# CH1_CH2.net
KiCad netlist of a schematic drawn in Altium Designer
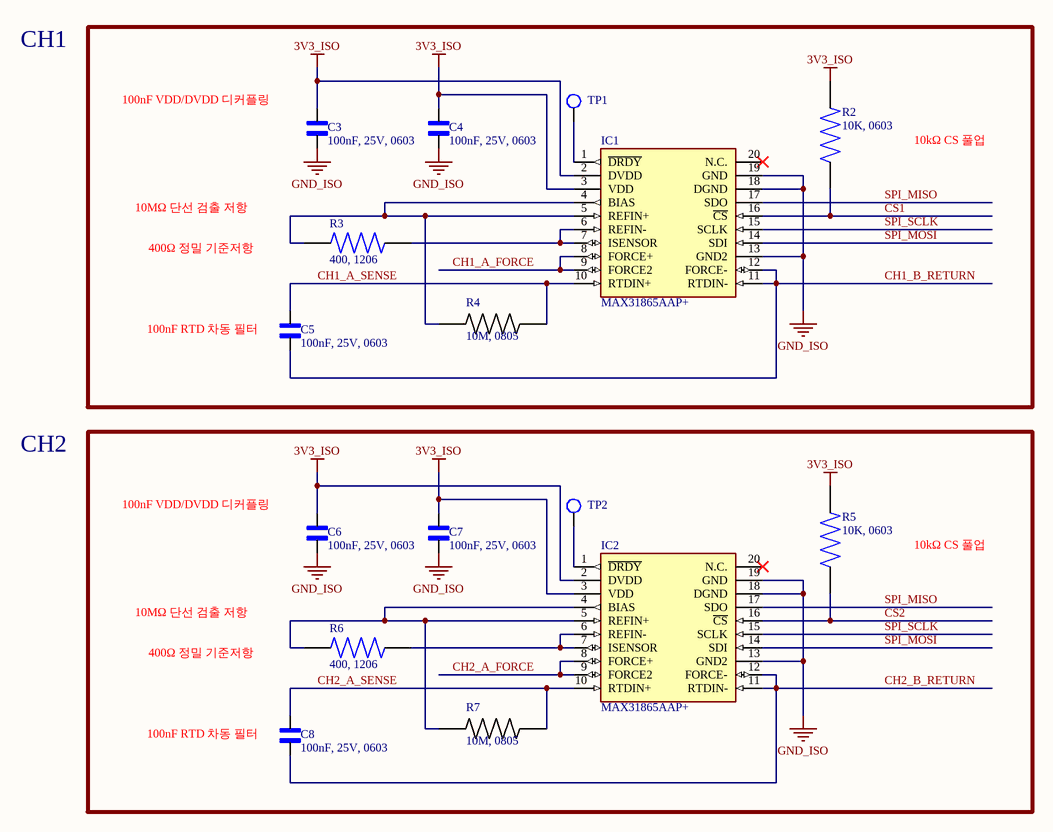
[diagram p0: CH1_CH2.SchDoc]

(export (version "E")
  (design (tool "Eeschema 10.0.6"))
  (components
    (comp (ref "C3")
      (value "100nF, 25V, 0603")
      (footprint "CAPC1608X90N")
      (description "Multilayer Ceramic Capacitors MLCC - SMD/SMT")
      (fields (field (name "MF") "Samsung Electro-Mechanics") (field (name "MP") "CL10B104KA8VPJC"))
      (libsource (lib "CL10B104KA8VPJC") (part "CL10B104KA8VPJC"))
    )
    (comp (ref "C4")
      (value "100nF, 25V, 0603")
      (footprint "CAPC1608X90N")
      (description "Multilayer Ceramic Capacitors MLCC - SMD/SMT")
      (fields (field (name "MF") "Samsung Electro-Mechanics") (field (name "MP") "CL10B104KA8VPJC"))
      (libsource (lib "CL10B104KA8VPJC") (part "CL10B104KA8VPJC"))
    )
    (comp (ref "C5")
      (value "100nF, 25V, 0603")
      (footprint "CAPC1608X90N")
      (description "Multilayer Ceramic Capacitors MLCC - SMD/SMT")
      (fields (field (name "MF") "Samsung Electro-Mechanics") (field (name "MP") "CL10B104KA8VPJC"))
      (libsource (lib "CL10B104KA8VPJC") (part "CL10B104KA8VPJC"))
    )
    (comp (ref "C6")
      (value "100nF, 25V, 0603")
      (footprint "CAPC1608X90N")
      (description "Multilayer Ceramic Capacitors MLCC - SMD/SMT")
      (fields (field (name "MF") "Samsung Electro-Mechanics") (field (name "MP") "CL10B104KA8VPJC"))
      (libsource (lib "CL10B104KA8VPJC") (part "CL10B104KA8VPJC"))
    )
    (comp (ref "C7")
      (value "100nF, 25V, 0603")
      (footprint "CAPC1608X90N")
      (description "Multilayer Ceramic Capacitors MLCC - SMD/SMT")
      (fields (field (name "MF") "Samsung Electro-Mechanics") (field (name "MP") "CL10B104KA8VPJC"))
      (libsource (lib "CL10B104KA8VPJC") (part "CL10B104KA8VPJC"))
    )
    (comp (ref "C8")
      (value "100nF, 25V, 0603")
      (footprint "CAPC1608X90N")
      (description "Multilayer Ceramic Capacitors MLCC - SMD/SMT")
      (fields (field (name "MF") "Samsung Electro-Mechanics") (field (name "MP") "CL10B104KA8VPJC"))
      (libsource (lib "CL10B104KA8VPJC") (part "CL10B104KA8VPJC"))
    )
    (comp (ref "IC1")
      (value "MAX31865AAP+")
      (footprint "SamacSys:SOP65P778X199-20N")
      (description "Integrated Circuit")
      (fields (field (name "MOUSER PART NUMBER") "700-MAX31865AAP+"))
      (libsource (lib "MAX31865AAP+") (part "MAX31865AAP+"))
    )
    (comp (ref "IC2")
      (value "MAX31865AAP+")
      (footprint "SamacSys:SOP65P778X199-20N")
      (description "Integrated Circuit")
      (fields (field (name "MOUSER PART NUMBER") "700-MAX31865AAP+"))
      (libsource (lib "MAX31865AAP+") (part "MAX31865AAP+"))
    )
    (comp (ref "R2")
      (value "10K, 0603")
      (footprint "RESC1607X60N")
      (description "10 kOhms ±1% 0.1W, 1/10W Chip Resistor 0603 (1608 Metric) Moisture Resistant Thick Film")
      (fields (field (name "MF") "Yageo Corporation") (field (name "MP") "RC0603FR0710KL"))
      (libsource (lib "RC0603FR-0710KL") (part "RC0603FR-0710KL"))
    )
    (comp (ref "R3")
      (value "400, 1206")
      (footprint "RESC3116X65N")
      (description "400 Ohms Â±0.1% 0.25W, 1/4W Chip Resistor 1206 (3216 Metric) - Thin Film")
      (fields (field (name "MF") "Yageo") (field (name "MP") "RT1206BRD07400RL"))
      (libsource (lib "RT1206BRD07400RL") (part "RT1206BRD07400RL"))
    )
    (comp (ref "R4")
      (value "10M, 0805")
      (footprint "*RESC2012X60N")
      (description "10MΩ, ±1%, 125mW, 0805, AEC-Q200")
      (libsource (lib "AC0805FR-1010ML") (part "AC0805FR-1010ML"))
    )
    (comp (ref "R5")
      (value "10K, 0603")
      (footprint "RESC1607X60N")
      (description "10 kOhms ±1% 0.1W, 1/10W Chip Resistor 0603 (1608 Metric) Moisture Resistant Thick Film")
      (fields (field (name "MF") "Yageo Corporation") (field (name "MP") "RC0603FR0710KL"))
      (libsource (lib "RC0603FR-0710KL") (part "RC0603FR-0710KL"))
    )
    (comp (ref "R6")
      (value "400, 1206")
      (footprint "RESC3116X65N")
      (description "400 Ohms Â±0.1% 0.25W, 1/4W Chip Resistor 1206 (3216 Metric) - Thin Film")
      (fields (field (name "MF") "Yageo") (field (name "MP") "RT1206BRD07400RL"))
      (libsource (lib "RT1206BRD07400RL") (part "RT1206BRD07400RL"))
    )
    (comp (ref "R7")
      (value "10M, 0805")
      (footprint "*RESC2012X60N")
      (description "10MΩ, ±1%, 125mW, 0805, AEC-Q200")
      (libsource (lib "AC0805FR-1010ML") (part "AC0805FR-1010ML"))
    )
    (comp (ref "TP1")
      (value "TEST POINT")
      (footprint "TESTPOINT")
      (libsource (lib "TP1.0-SMD") (part "TEST POINT"))
    )
    (comp (ref "TP2")
      (value "TEST POINT")
      (footprint "TESTPOINT")
      (libsource (lib "TP1.0-SMD") (part "TEST POINT"))
    )
  )
  (nets
    (net (code "1") (name "/CH1_A_FORCE") (class "Default")
      (node (ref "IC1") (pin "8") (pinfunction "FORCE+_8") (pintype "bidirectional"))
      (node (ref "IC1") (pin "9") (pinfunction "FORCE2_9") (pintype "bidirectional"))
    )
    (net (code "2") (name "/CH1_A_SENSE") (class "Default")
      (node (ref "C5") (pin "2") (pinfunction "2_2") (pintype "passive"))
      (node (ref "IC1") (pin "10") (pinfunction "RTDIN+_10") (pintype "input"))
      (node (ref "R4") (pin "2") (pinfunction "2_2") (pintype "passive"))
    )
    (net (code "3") (name "/CH1_B_RETURN") (class "Default")
      (node (ref "C5") (pin "1") (pinfunction "1_1") (pintype "passive"))
      (node (ref "IC1") (pin "11") (pinfunction "RTDIN-_11") (pintype "input"))
      (node (ref "IC1") (pin "12") (pinfunction "FORCE-_12") (pintype "bidirectional"))
    )
    (net (code "4") (name "/CH2_A_FORCE") (class "Default")
      (node (ref "IC2") (pin "8") (pinfunction "FORCE+_8") (pintype "bidirectional"))
      (node (ref "IC2") (pin "9") (pinfunction "FORCE2_9") (pintype "bidirectional"))
    )
    (net (code "5") (name "/CH2_A_SENSE") (class "Default")
      (node (ref "C8") (pin "2") (pinfunction "2_2") (pintype "passive"))
      (node (ref "IC2") (pin "10") (pinfunction "RTDIN+_10") (pintype "input"))
      (node (ref "R7") (pin "2") (pinfunction "2_2") (pintype "passive"))
    )
    (net (code "6") (name "/CH2_B_RETURN") (class "Default")
      (node (ref "C8") (pin "1") (pinfunction "1_1") (pintype "passive"))
      (node (ref "IC2") (pin "11") (pinfunction "RTDIN-_11") (pintype "input"))
      (node (ref "IC2") (pin "12") (pinfunction "FORCE-_12") (pintype "bidirectional"))
    )
    (net (code "7") (name "/CS1") (class "Default")
      (node (ref "IC1") (pin "16") (pinfunction "~{CS}_16") (pintype "input"))
      (node (ref "R2") (pin "1") (pinfunction "1_1") (pintype "passive"))
    )
    (net (code "8") (name "/CS2") (class "Default")
      (node (ref "IC2") (pin "16") (pinfunction "~{CS}_16") (pintype "input"))
      (node (ref "R5") (pin "1") (pinfunction "1_1") (pintype "passive"))
    )
    (net (code "9") (name "/SPI_MISO") (class "Default")
      (node (ref "IC1") (pin "17") (pinfunction "SDO_17") (pintype "tri_state"))
      (node (ref "IC2") (pin "17") (pinfunction "SDO_17") (pintype "tri_state"))
    )
    (net (code "10") (name "/SPI_MOSI") (class "Default")
      (node (ref "IC1") (pin "14") (pinfunction "SDI_14") (pintype "input"))
      (node (ref "IC2") (pin "14") (pinfunction "SDI_14") (pintype "input"))
    )
    (net (code "11") (name "/SPI_SCLK") (class "Default")
      (node (ref "IC1") (pin "15") (pinfunction "SCLK_15") (pintype "input"))
      (node (ref "IC2") (pin "15") (pinfunction "SCLK_15") (pintype "input"))
    )
    (net (code "12") (name "3V3_ISO") (class "Default")
      (node (ref "C3") (pin "2") (pinfunction "2_2") (pintype "passive"))
      (node (ref "C4") (pin "2") (pinfunction "2_2") (pintype "passive"))
      (node (ref "C6") (pin "2") (pinfunction "2_2") (pintype "passive"))
      (node (ref "C7") (pin "2") (pinfunction "2_2") (pintype "passive"))
      (node (ref "IC1") (pin "2") (pinfunction "DVDD_2") (pintype "power_in"))
      (node (ref "IC1") (pin "3") (pinfunction "VDD_3") (pintype "power_in"))
      (node (ref "IC2") (pin "2") (pinfunction "DVDD_2") (pintype "power_in"))
      (node (ref "IC2") (pin "3") (pinfunction "VDD_3") (pintype "power_in"))
      (node (ref "R2") (pin "2") (pinfunction "2_2") (pintype "passive"))
      (node (ref "R5") (pin "2") (pinfunction "2_2") (pintype "passive"))
    )
    (net (code "13") (name "GND_ISO") (class "Default")
      (node (ref "C3") (pin "1") (pinfunction "1_1") (pintype "passive"))
      (node (ref "C4") (pin "1") (pinfunction "1_1") (pintype "passive"))
      (node (ref "C6") (pin "1") (pinfunction "1_1") (pintype "passive"))
      (node (ref "C7") (pin "1") (pinfunction "1_1") (pintype "passive"))
      (node (ref "IC1") (pin "13") (pinfunction "GND2_13") (pintype "power_in"))
      (node (ref "IC1") (pin "18") (pinfunction "DGND_18") (pintype "power_in"))
      (node (ref "IC1") (pin "19") (pinfunction "GND_19") (pintype "power_in"))
      (node (ref "IC2") (pin "13") (pinfunction "GND2_13") (pintype "power_in"))
      (node (ref "IC2") (pin "18") (pinfunction "DGND_18") (pintype "power_in"))
      (node (ref "IC2") (pin "19") (pinfunction "GND_19") (pintype "power_in"))
    )
    (net (code "14") (name "Net-(IC1-BIAS)") (class "Default")
      (node (ref "IC1") (pin "4") (pinfunction "BIAS_4") (pintype "output"))
      (node (ref "IC1") (pin "5") (pinfunction "REFIN+_5") (pintype "input"))
      (node (ref "R3") (pin "1") (pinfunction "1_1") (pintype "passive"))
      (node (ref "R4") (pin "1") (pinfunction "1_1") (pintype "passive"))
    )
    (net (code "15") (name "Net-(IC1-ISENSOR)") (class "Default")
      (node (ref "IC1") (pin "6") (pinfunction "REFIN-_6") (pintype "input"))
      (node (ref "IC1") (pin "7") (pinfunction "ISENSOR_7") (pintype "bidirectional"))
      (node (ref "R3") (pin "2") (pinfunction "2_2") (pintype "passive"))
    )
    (net (code "16") (name "Net-(IC1-~{DRDY})") (class "Default")
      (node (ref "IC1") (pin "1") (pinfunction "~{DRDY}_1") (pintype "output"))
      (node (ref "TP1") (pin "1") (pinfunction "1_1") (pintype "passive"))
    )
    (net (code "17") (name "Net-(IC2-BIAS)") (class "Default")
      (node (ref "IC2") (pin "4") (pinfunction "BIAS_4") (pintype "output"))
      (node (ref "IC2") (pin "5") (pinfunction "REFIN+_5") (pintype "input"))
      (node (ref "R6") (pin "1") (pinfunction "1_1") (pintype "passive"))
      (node (ref "R7") (pin "1") (pinfunction "1_1") (pintype "passive"))
    )
    (net (code "18") (name "Net-(IC2-ISENSOR)") (class "Default")
      (node (ref "IC2") (pin "6") (pinfunction "REFIN-_6") (pintype "input"))
      (node (ref "IC2") (pin "7") (pinfunction "ISENSOR_7") (pintype "bidirectional"))
      (node (ref "R6") (pin "2") (pinfunction "2_2") (pintype "passive"))
    )
    (net (code "19") (name "Net-(IC2-~{DRDY})") (class "Default")
      (node (ref "IC2") (pin "1") (pinfunction "~{DRDY}_1") (pintype "output"))
      (node (ref "TP2") (pin "1") (pinfunction "1_1") (pintype "passive"))
    )
    (net (code "20") (name "unconnected-(IC1-N.C.-Pad20)") (class "Default")
      (node (ref "IC1") (pin "20") (pinfunction "N.C._20") (pintype "passive+no_connect"))
    )
    (net (code "21") (name "unconnected-(IC2-N.C.-Pad20)") (class "Default")
      (node (ref "IC2") (pin "20") (pinfunction "N.C._20") (pintype "passive+no_connect"))
    )
  )
)
